# Mailbox_Notifier_2_2.net
KiCad netlist of a schematic drawn in EAGLE
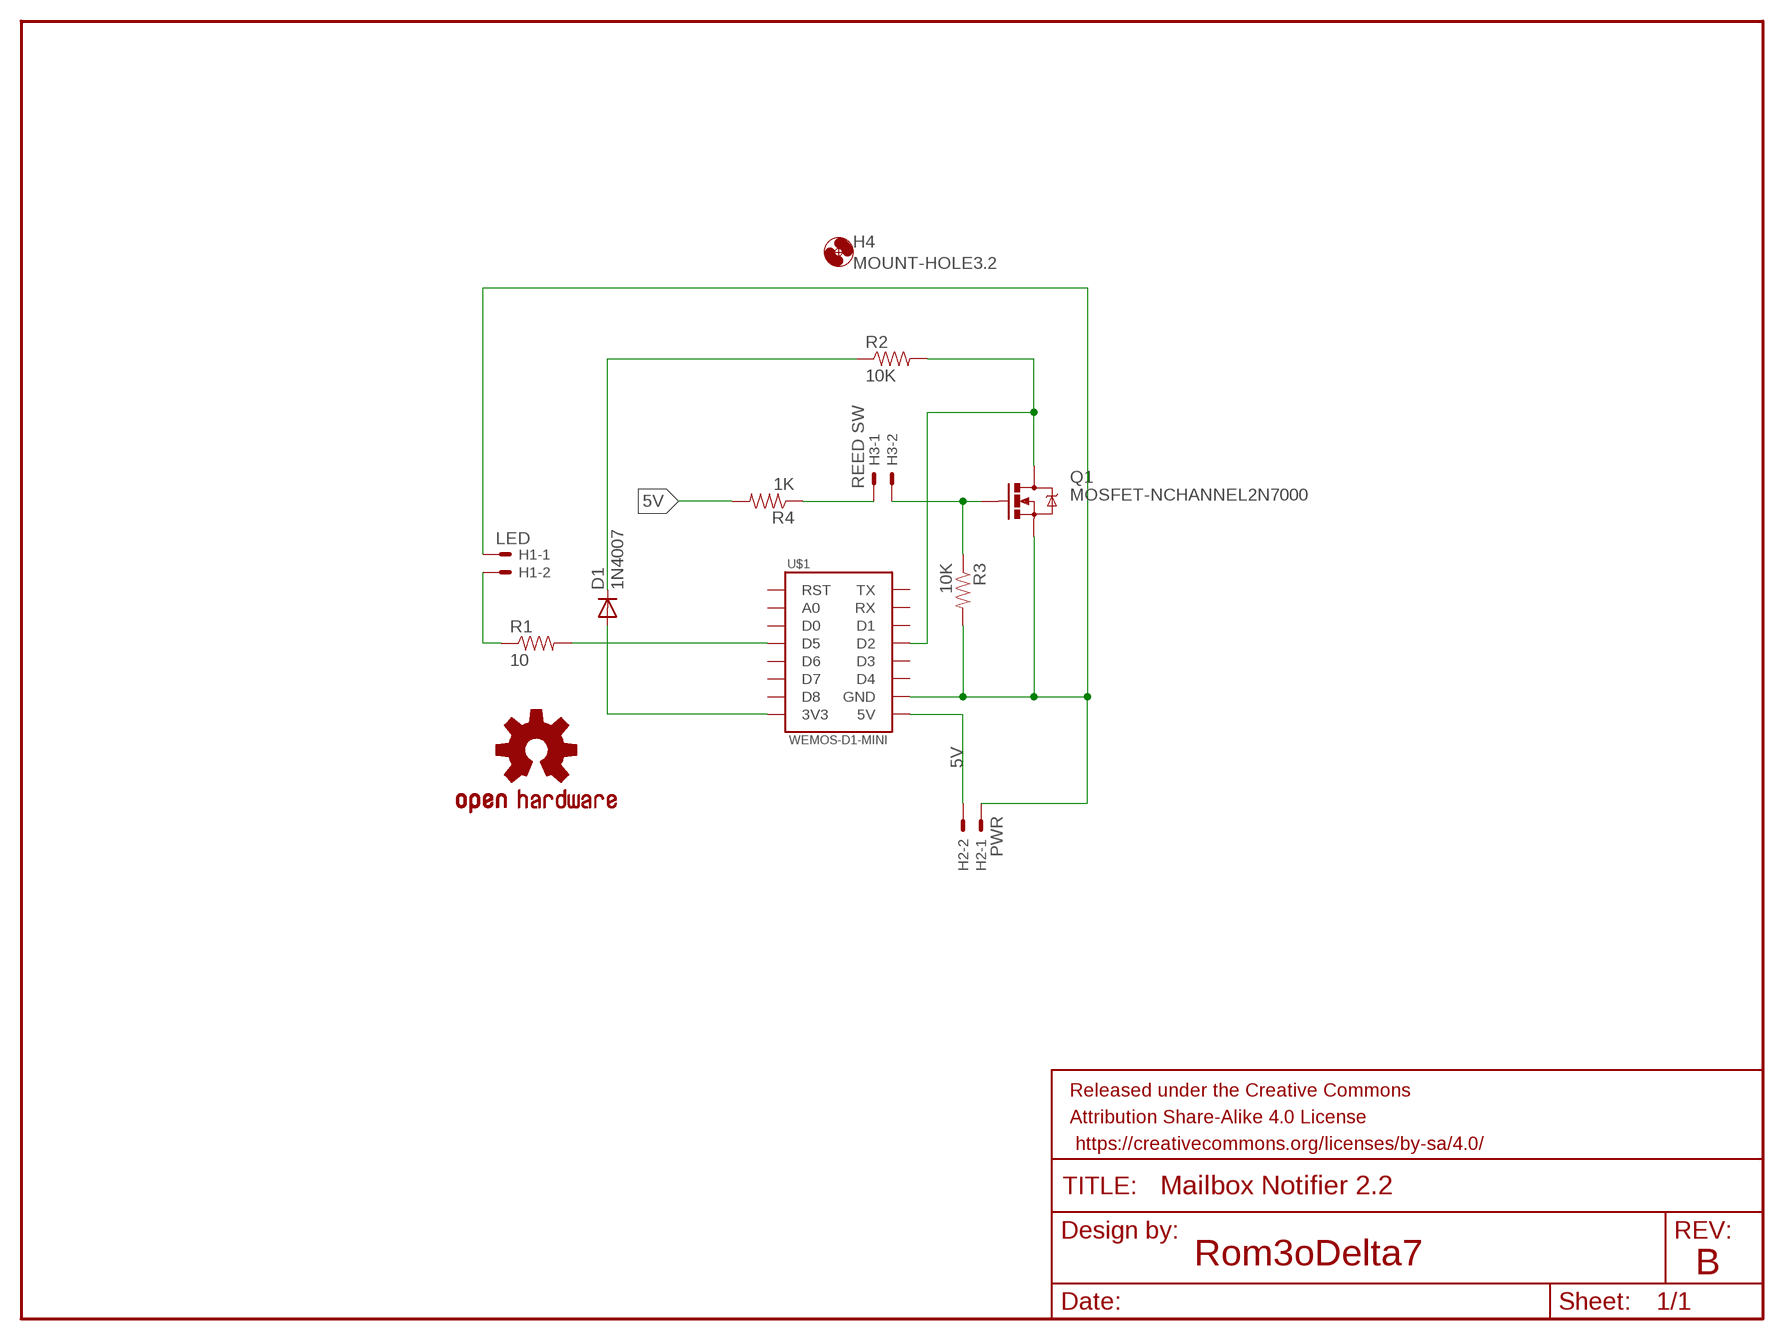
[diagram p0: schematic, sheet 1]

(export (version "E")
  (design (tool "Eeschema 10.0.6"))
  (components
    (comp (ref "D1")
      (value "1N4007")
      (footprint "eagle-import:DO41-10")
      (libsource (lib "eagle-import") (part "1N4004"))
    )
    (comp (ref "FRAME1")
      (value "FRAME-LETTER")
      (footprint "eagle-import:CREATIVE_COMMONS")
      (libsource (lib "eagle-import") (part "FRAME-LETTER"))
    )
    (comp (ref "H1")
      (value "LED")
      (footprint "eagle-import:22-23-2021")
      (fields (field (name "MF") "MOLEX") (field (name "MPN") "22-23-2021"))
      (libsource (lib "eagle-import") (part "22-23-2021"))
    )
    (comp (ref "H2")
      (value "PWR")
      (footprint "eagle-import:22-23-2021")
      (fields (field (name "MF") "MOLEX") (field (name "MPN") "22-23-2021"))
      (libsource (lib "eagle-import") (part "22-23-2021"))
    )
    (comp (ref "H3")
      (value "REED SW")
      (footprint "eagle-import:22-23-2021")
      (fields (field (name "MF") "MOLEX") (field (name "MPN") "22-23-2021"))
      (libsource (lib "eagle-import") (part "22-23-2021"))
    )
    (comp (ref "H4")
      (value "MOUNT-HOLE3.2")
      (footprint "eagle-import:3,2")
      (libsource (lib "eagle-import") (part "MOUNT-HOLE3.2"))
    )
    (comp (ref "LOGO1")
      (value "OSHW-LOGOMINI")
      (footprint "eagle-import:OSHW-LOGO-MINI")
      (libsource (lib "eagle-import") (part "OSHW-LOGOMINI"))
    )
    (comp (ref "Q1")
      (value "MOSFET-NCHANNEL2N7000")
      (footprint "eagle-import:TO-92")
      (libsource (lib "eagle-import") (part "MOSFET-NCHANNEL2N7000"))
    )
    (comp (ref "R1")
      (value "10")
      (footprint "eagle-import:AXIAL-0.5")
      (libsource (lib "eagle-import") (part "RESISTORPTH-1/2W"))
    )
    (comp (ref "R2")
      (value "10K")
      (footprint "eagle-import:AXIAL-0.4")
      (libsource (lib "eagle-import") (part "RESISTORPTH-1/4W"))
    )
    (comp (ref "R3")
      (value "10K")
      (footprint "eagle-import:AXIAL-0.4")
      (libsource (lib "eagle-import") (part "RESISTORPTH-1/4W"))
    )
    (comp (ref "R4")
      (value "1K")
      (footprint "eagle-import:AXIAL-0.4")
      (libsource (lib "eagle-import") (part "RESISTORPTH-1/4W"))
    )
    (comp (ref "U$1")
      (value "WEMOS-D1-MINI")
      (footprint "eagle-import:WEMOS-D1-MINI")
      (libsource (lib "eagle-import") (part "WEMOS-D1-MINI"))
    )
  )
  (nets
    (net (code "1") (name "5V") (class "Default")
      (node (ref "H2") (pin "2") (pinfunction "S_2") (pintype "passive"))
      (node (ref "R4") (pin "P$2") (pinfunction "2_P$2") (pintype "passive"))
      (node (ref "U$1") (pin "5V") (pinfunction "5V_5V") (pintype "power_in"))
    )
    (net (code "2") (name "Net-(D1-PadA)") (class "Default")
      (node (ref "D1") (pin "A") (pinfunction "A_A") (pintype "passive"))
      (node (ref "U$1") (pin "3V3") (pinfunction "3V3_3V3") (pintype "power_in"))
    )
    (net (code "3") (name "Net-(H1A-S)") (class "Default")
      (node (ref "H1") (pin "1") (pinfunction "S_1") (pintype "passive"))
      (node (ref "H2") (pin "1") (pinfunction "S_1") (pintype "passive"))
      (node (ref "Q1") (pin "1") (pinfunction "S_1") (pintype "passive"))
      (node (ref "R3") (pin "P$2") (pinfunction "2_P$2") (pintype "passive"))
      (node (ref "U$1") (pin "GND") (pinfunction "GND_GND") (pintype "power_in"))
    )
    (net (code "4") (name "Net-(H1B-S)") (class "Default")
      (node (ref "H1") (pin "2") (pinfunction "S_2") (pintype "passive"))
      (node (ref "R1") (pin "P$1") (pinfunction "1_P$1") (pintype "passive"))
    )
    (net (code "5") (name "Net-(H3A-S)") (class "Default")
      (node (ref "H3") (pin "1") (pinfunction "S_1") (pintype "passive"))
      (node (ref "R4") (pin "P$1") (pinfunction "1_P$1") (pintype "passive"))
    )
    (net (code "6") (name "Net-(H3B-S)") (class "Default")
      (node (ref "H3") (pin "2") (pinfunction "S_2") (pintype "passive"))
      (node (ref "Q1") (pin "2") (pinfunction "G_2") (pintype "passive"))
      (node (ref "R3") (pin "P$1") (pinfunction "1_P$1") (pintype "passive"))
    )
    (net (code "7") (name "Net-(Q1-D)") (class "Default")
      (node (ref "Q1") (pin "3") (pinfunction "D_3") (pintype "passive"))
      (node (ref "R2") (pin "P$2") (pinfunction "2_P$2") (pintype "passive"))
      (node (ref "U$1") (pin "D2") (pinfunction "D2_D2") (pintype "bidirectional"))
    )
    (net (code "8") (name "Net-(R1-2)") (class "Default")
      (node (ref "R1") (pin "P$2") (pinfunction "2_P$2") (pintype "passive"))
      (node (ref "U$1") (pin "D5") (pinfunction "D5_D5") (pintype "bidirectional"))
    )
    (net (code "9") (name "Net-(R2-1)") (class "Default")
      (node (ref "D1") (pin "C") (pinfunction "C_C") (pintype "passive"))
      (node (ref "R2") (pin "P$1") (pinfunction "1_P$1") (pintype "passive"))
    )
    (net (code "10") (name "unconnected-(U$1-PadA0)") (class "Default")
      (node (ref "U$1") (pin "A0") (pinfunction "A0_A0") (pintype "input"))
    )
    (net (code "11") (name "unconnected-(U$1-PadD0)") (class "Default")
      (node (ref "U$1") (pin "D0") (pinfunction "D0_D0") (pintype "bidirectional"))
    )
    (net (code "12") (name "unconnected-(U$1-PadD1)") (class "Default")
      (node (ref "U$1") (pin "D1") (pinfunction "D1_D1") (pintype "bidirectional"))
    )
    (net (code "13") (name "unconnected-(U$1-PadD3)") (class "Default")
      (node (ref "U$1") (pin "D3") (pinfunction "D3_D3") (pintype "bidirectional"))
    )
    (net (code "14") (name "unconnected-(U$1-PadD4)") (class "Default")
      (node (ref "U$1") (pin "D4") (pinfunction "D4_D4") (pintype "bidirectional"))
    )
    (net (code "15") (name "unconnected-(U$1-PadD6)") (class "Default")
      (node (ref "U$1") (pin "D6") (pinfunction "D6_D6") (pintype "bidirectional"))
    )
    (net (code "16") (name "unconnected-(U$1-PadD7)") (class "Default")
      (node (ref "U$1") (pin "D7") (pinfunction "D7_D7") (pintype "bidirectional"))
    )
    (net (code "17") (name "unconnected-(U$1-PadD8)") (class "Default")
      (node (ref "U$1") (pin "D8") (pinfunction "D8_D8") (pintype "bidirectional"))
    )
    (net (code "18") (name "unconnected-(U$1-PadRST)") (class "Default")
      (node (ref "U$1") (pin "RST") (pinfunction "RST_RST") (pintype "input"))
    )
    (net (code "19") (name "unconnected-(U$1-PadRX)") (class "Default")
      (node (ref "U$1") (pin "RX") (pinfunction "RX_RX") (pintype "input"))
    )
    (net (code "20") (name "unconnected-(U$1-PadTX)") (class "Default")
      (node (ref "U$1") (pin "TX") (pinfunction "TX_TX") (pintype "output"))
    )
  )
)
